# Buck_Converter.net
KiCad netlist of a schematic drawn in Altium Designer
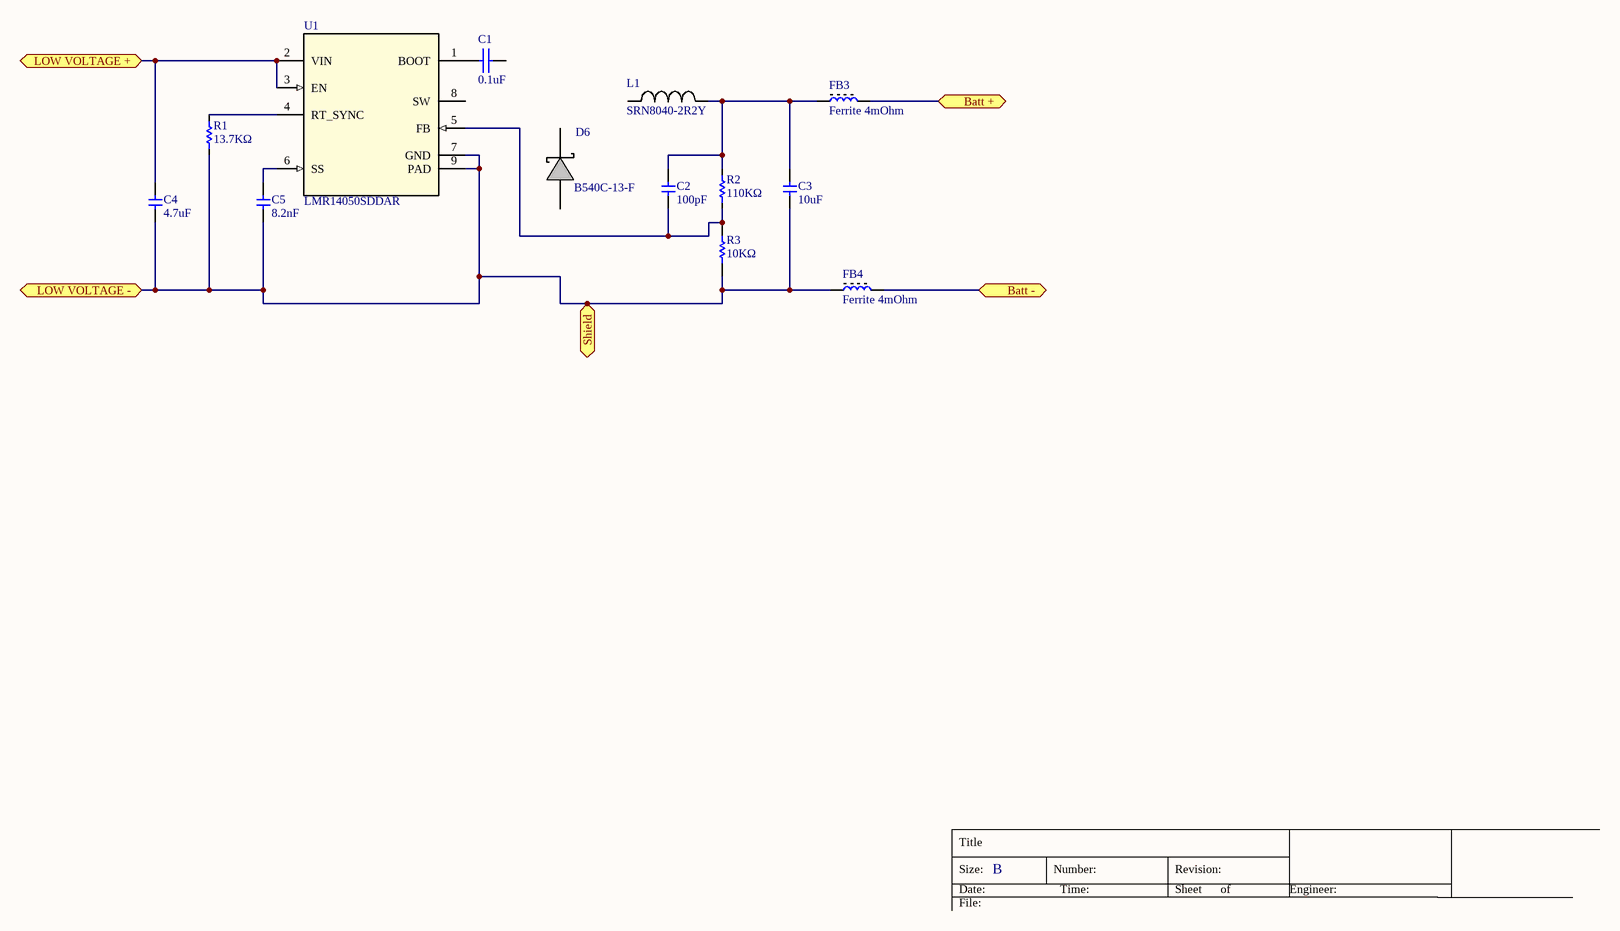
[diagram p0: Buck Converter.SchDoc]

(export (version "E")
  (design (tool "Eeschema 10.0.6"))
  (components
    (comp (ref "C1")
      (value "0.1uF")
      (footprint "0603 Small")
      (description "CAP CER 0.1UF 50V 10% X7R 0603")
      (fields (field (name "MANUFACTURER") "Murata Electronics"))
      (libsource (lib "sch protel") (part "CAP"))
    )
    (comp (ref "C2")
      (value "100pF")
      (footprint "0603 Capacitor")
      (description "100pF ±10% 16V Ceramic Capacitor X7R 0201 (0603 Metric)")
      (fields (field (name "MANUFACTURER") "Murata Electronics North America"))
      (libsource (lib "Curtis") (part "Cap"))
    )
    (comp (ref "C3")
      (value "10uF")
      (footprint "0805 capacitor")
      (description "10µF ±10% 16V Ceramic Capacitor X5R 0805 (2012 Metric)")
      (fields (field (name "MANUFACTURER") "Murata Electronics North America"))
      (libsource (lib "Curtis") (part "Cap"))
    )
    (comp (ref "C4")
      (value "4.7uF")
      (footprint "1206 - duplicate")
      (description "4.7µF ±10% 50V Ceramic Capacitor X7R 1206 (3216 Metric)")
      (fields (field (name "MANUFACTURER") "Taiyo Yuden"))
      (libsource (lib "Curtis") (part "Cap"))
    )
    (comp (ref "C5")
      (value "8.2nF")
      (footprint "0402 Small")
      (description "8200pF ±10% 16V Ceramic Capacitor X7R 0402 (1005 Metric)")
      (fields (field (name "MANUFACTURER") "Murata Electronics North America"))
      (libsource (lib "Curtis") (part "Cap"))
    )
    (comp (ref "D6")
      (value "B540C-13-F")
      (footprint "SMC")
      (description "DIODE SCHOTTKY 40V 5A SMC")
      (fields (field (name "MANUFACTURER") "Diodes Incorporated"))
      (libsource (lib "Curtis") (part "B540C-13-F"))
    )
    (comp (ref "FB3")
      (value "Ferrite 4mOhm")
      (footprint "0603 Inductor")
      (fields (field (name "MANUFACTURER") "Murata Electronics North America"))
      (libsource (lib "Curtis") (part "Ferrite Bead"))
    )
    (comp (ref "FB4")
      (value "Ferrite 4mOhm")
      (footprint "0603 Inductor")
      (fields (field (name "MANUFACTURER") "Murata Electronics North America"))
      (libsource (lib "Curtis") (part "Ferrite Bead"))
    )
    (comp (ref "L1")
      (value "SRN8040-2R2Y")
      (footprint "SRN8040 - Power Inductor")
      (description "2.2µH Shielded Wirewound Inductor 6.3A 13 mOhm Max Nonstandard")
      (fields (field (name "MANUFACTURER") "Bourns"))
      (libsource (lib "Curtis") (part "SRN8040-2R2Y"))
    )
    (comp (ref "R1")
      (value "13.7KΩ")
      (footprint "0402 Small")
      (description "13.7k Ohm ±1% 0.063W, 1/16W Chip Resistor 0402 (1005 Metric) Automotive AEC-Q200 Thick Film")
      (fields (field (name "MANUFACTURER") "Vishay Dale"))
      (libsource (lib "Curtis") (part "Resistor"))
    )
    (comp (ref "R2")
      (value "110KΩ")
      (footprint "0603 Small")
      (description "110k Ohm ±1% 0.1W, 1/10W Chip Resistor 0603 (1608 Metric) Moisture Resistant Thick Film")
      (fields (field (name "MANUFACTURER") "Yageo"))
      (libsource (lib "Curtis") (part "Resistor"))
    )
    (comp (ref "R3")
      (value "10KΩ")
      (footprint "0603 Small")
      (description "Thick Film Resistors - SMD 0603 10Kohms 1% Tol")
      (fields (field (name "MANUFACTURER") "Panasonic"))
      (libsource (lib "Miscellaneous Devices") (part "Res1"))
    )
    (comp (ref "U1")
      (value "LMR14050SDDAR")
      (footprint "SO8 - GROUND PAD")
      (fields
        (field (name "MANUFACTURER") "Texas Instruments")
        (field (name "ALTERNATE_PARTNUMBER") "LMR14050SDDA")
      )
      (libsource (lib "Curtis") (part "LMR14050SDDAR"))
    )
  )
  (nets
    (net (code "1") (name "/Batt +") (class "Default")
      (node (ref "FB3") (pin "2") (pinfunction "2_2") (pintype "passive"))
    )
    (net (code "2") (name "/Batt -") (class "Default")
      (node (ref "FB4") (pin "2") (pinfunction "2_2") (pintype "passive"))
    )
    (net (code "3") (name "/LOW VOLTAGE +") (class "Default")
      (node (ref "C4") (pin "1") (pinfunction "1_1") (pintype "passive"))
      (node (ref "U1") (pin "2") (pinfunction "VIN_2") (pintype "power_in"))
      (node (ref "U1") (pin "3") (pinfunction "EN_3") (pintype "input"))
    )
    (net (code "4") (name "/LOW VOLTAGE -") (class "Default")
      (node (ref "C3") (pin "2") (pinfunction "2_2") (pintype "passive"))
      (node (ref "C4") (pin "2") (pinfunction "2_2") (pintype "passive"))
      (node (ref "C5") (pin "2") (pinfunction "2_2") (pintype "passive"))
      (node (ref "FB4") (pin "1") (pinfunction "1_1") (pintype "passive"))
      (node (ref "R1") (pin "1") (pinfunction "1_1") (pintype "passive"))
      (node (ref "R3") (pin "1") (pinfunction "1_1") (pintype "passive"))
      (node (ref "U1") (pin "7") (pinfunction "GND_7") (pintype "power_in"))
      (node (ref "U1") (pin "9") (pinfunction "PAD_9") (pintype "power_in"))
    )
    (net (code "5") (name "Net-(C2-Pad1)") (class "Default")
      (node (ref "C2") (pin "1") (pinfunction "1_1") (pintype "passive"))
      (node (ref "C3") (pin "1") (pinfunction "1_1") (pintype "passive"))
      (node (ref "FB3") (pin "1") (pinfunction "1_1") (pintype "passive"))
      (node (ref "L1") (pin "2") (pinfunction "2_2") (pintype "passive"))
      (node (ref "R2") (pin "2") (pinfunction "2_2") (pintype "passive"))
    )
    (net (code "6") (name "Net-(U1-BOOT)") (class "Default")
      (node (ref "C1") (pin "1") (pintype "passive"))
      (node (ref "U1") (pin "1") (pinfunction "BOOT_1") (pintype "passive"))
    )
    (net (code "7") (name "Net-(U1-FB)") (class "Default")
      (node (ref "C2") (pin "2") (pinfunction "2_2") (pintype "passive"))
      (node (ref "R2") (pin "1") (pinfunction "1_1") (pintype "passive"))
      (node (ref "R3") (pin "2") (pinfunction "2_2") (pintype "passive"))
      (node (ref "U1") (pin "5") (pinfunction "FB_5") (pintype "input"))
    )
    (net (code "8") (name "Net-(U1-RT_SYNC)") (class "Default")
      (node (ref "R1") (pin "2") (pinfunction "2_2") (pintype "passive"))
      (node (ref "U1") (pin "4") (pinfunction "RT_SYNC_4") (pintype "passive"))
    )
    (net (code "9") (name "Net-(U1-SS)") (class "Default")
      (node (ref "C5") (pin "1") (pinfunction "1_1") (pintype "passive"))
      (node (ref "U1") (pin "6") (pinfunction "SS_6") (pintype "input"))
    )
    (net (code "10") (name "unconnected-(C1-Pad2)") (class "Default")
      (node (ref "C1") (pin "2") (pintype "passive"))
    )
    (net (code "11") (name "unconnected-(D6-A-Pad2)") (class "Default")
      (node (ref "D6") (pin "2") (pinfunction "A_2") (pintype "passive"))
    )
    (net (code "12") (name "unconnected-(D6-K-Pad1)") (class "Default")
      (node (ref "D6") (pin "1") (pinfunction "K_1") (pintype "passive"))
    )
    (net (code "13") (name "unconnected-(L1-Pad1)") (class "Default")
      (node (ref "L1") (pin "1") (pinfunction "1_1") (pintype "passive"))
    )
    (net (code "14") (name "unconnected-(U1-SW-Pad8)") (class "Default")
      (node (ref "U1") (pin "8") (pinfunction "SW_8") (pintype "power_in"))
    )
  )
)
